# radiomodul.net
KiCad netlist of a schematic drawn in EAGLE
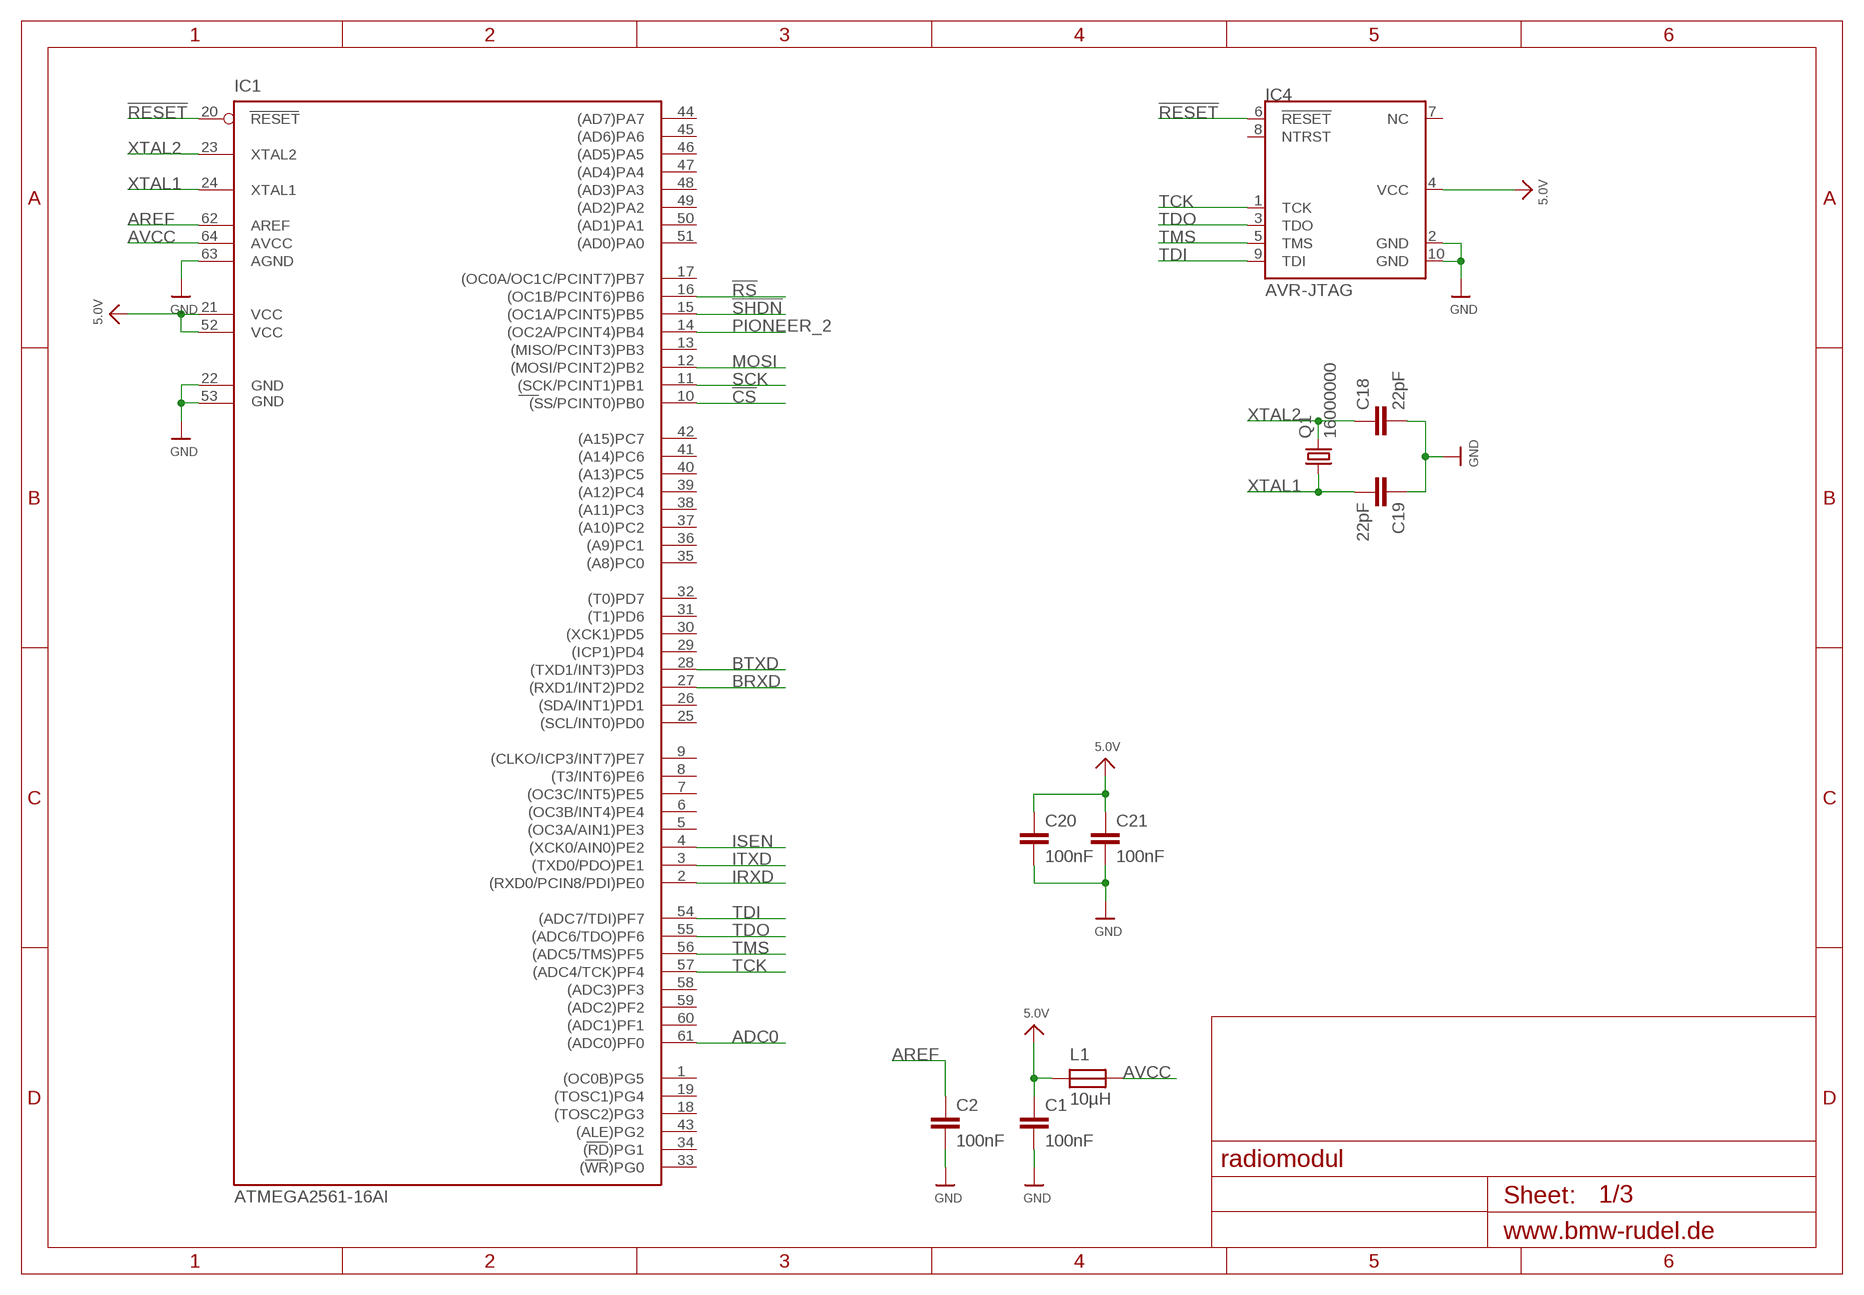
[diagram p0: schematic, sheet 1]
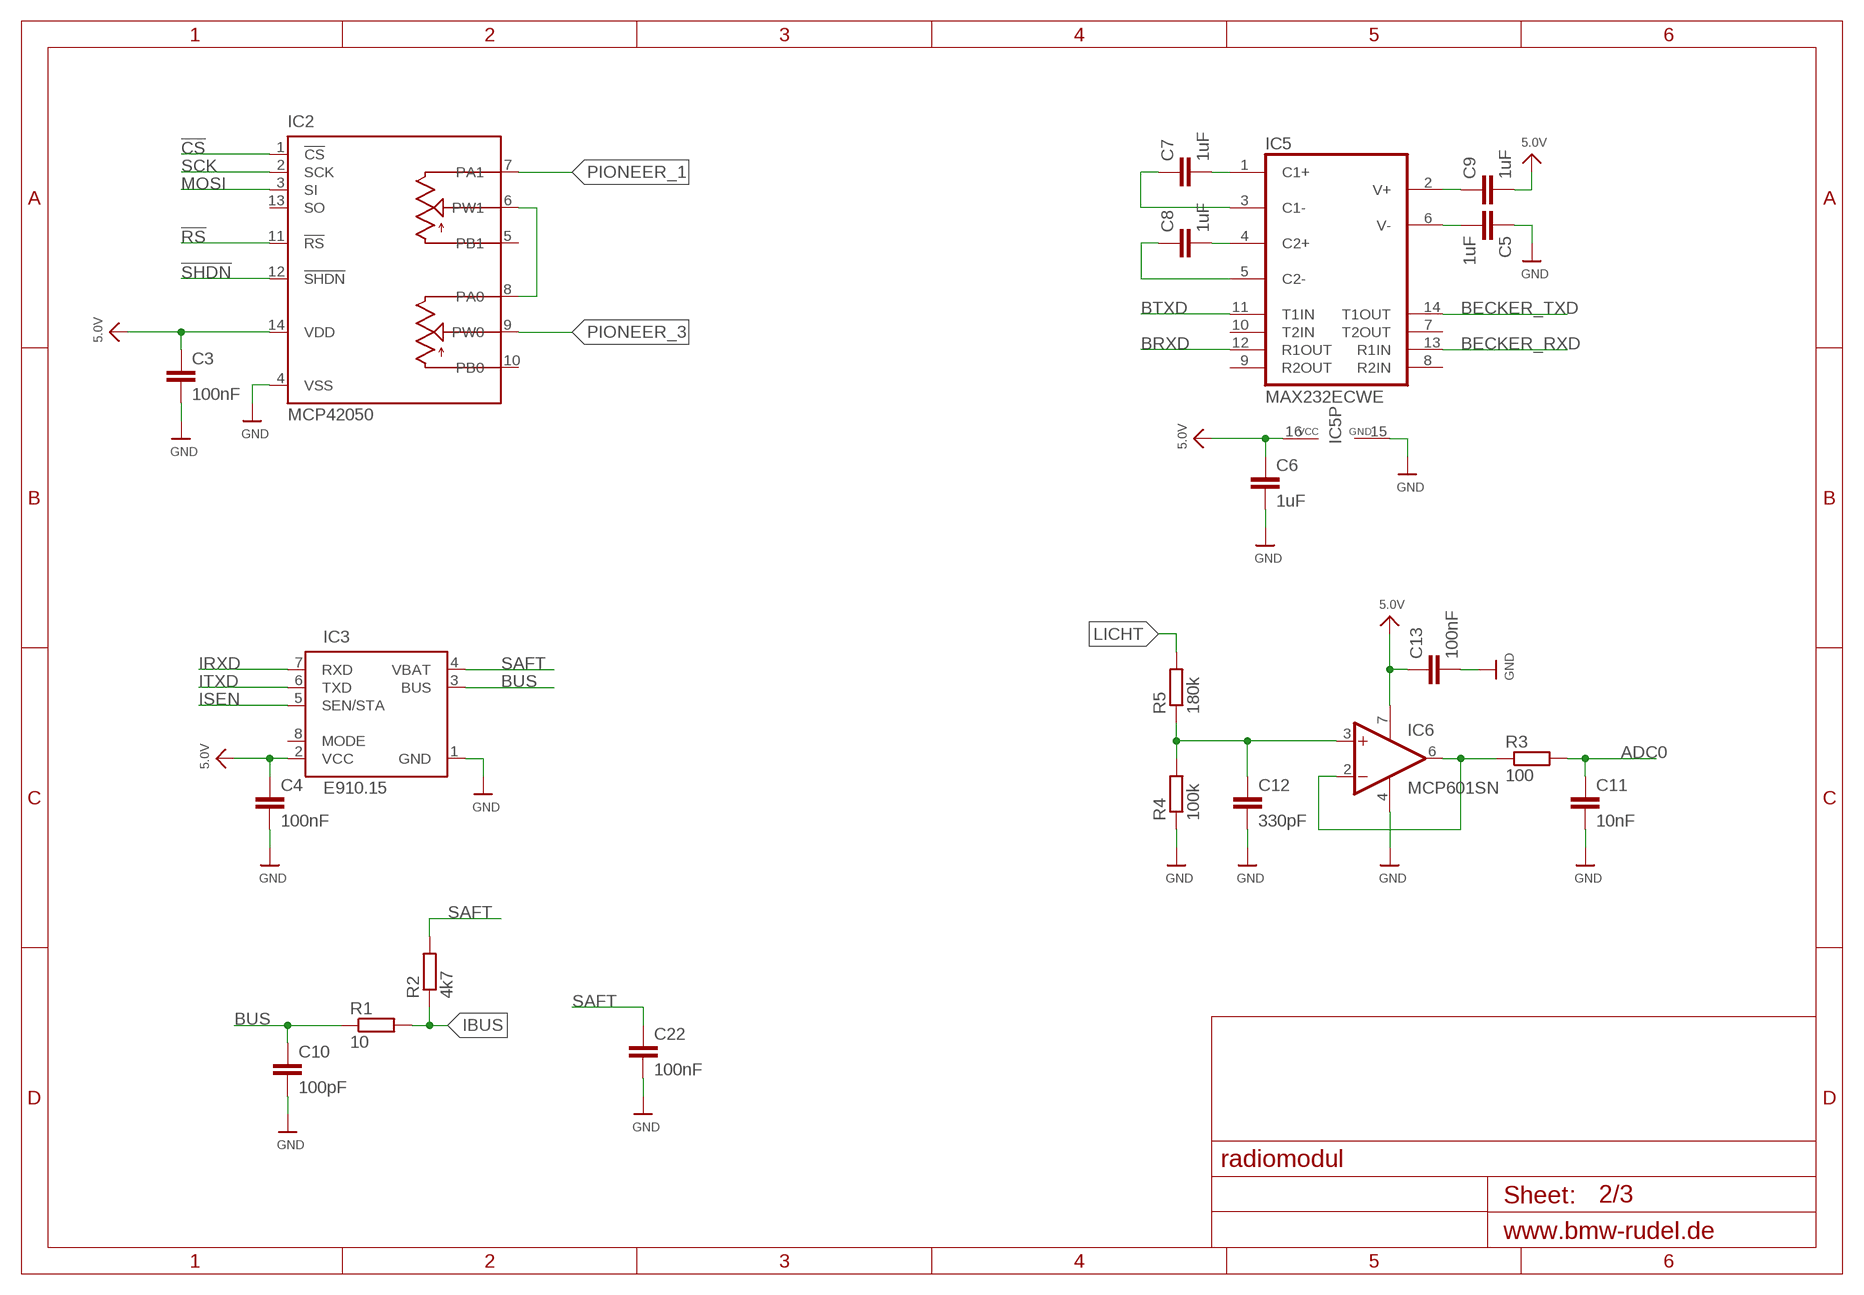
[diagram p1: schematic, sheet 2]
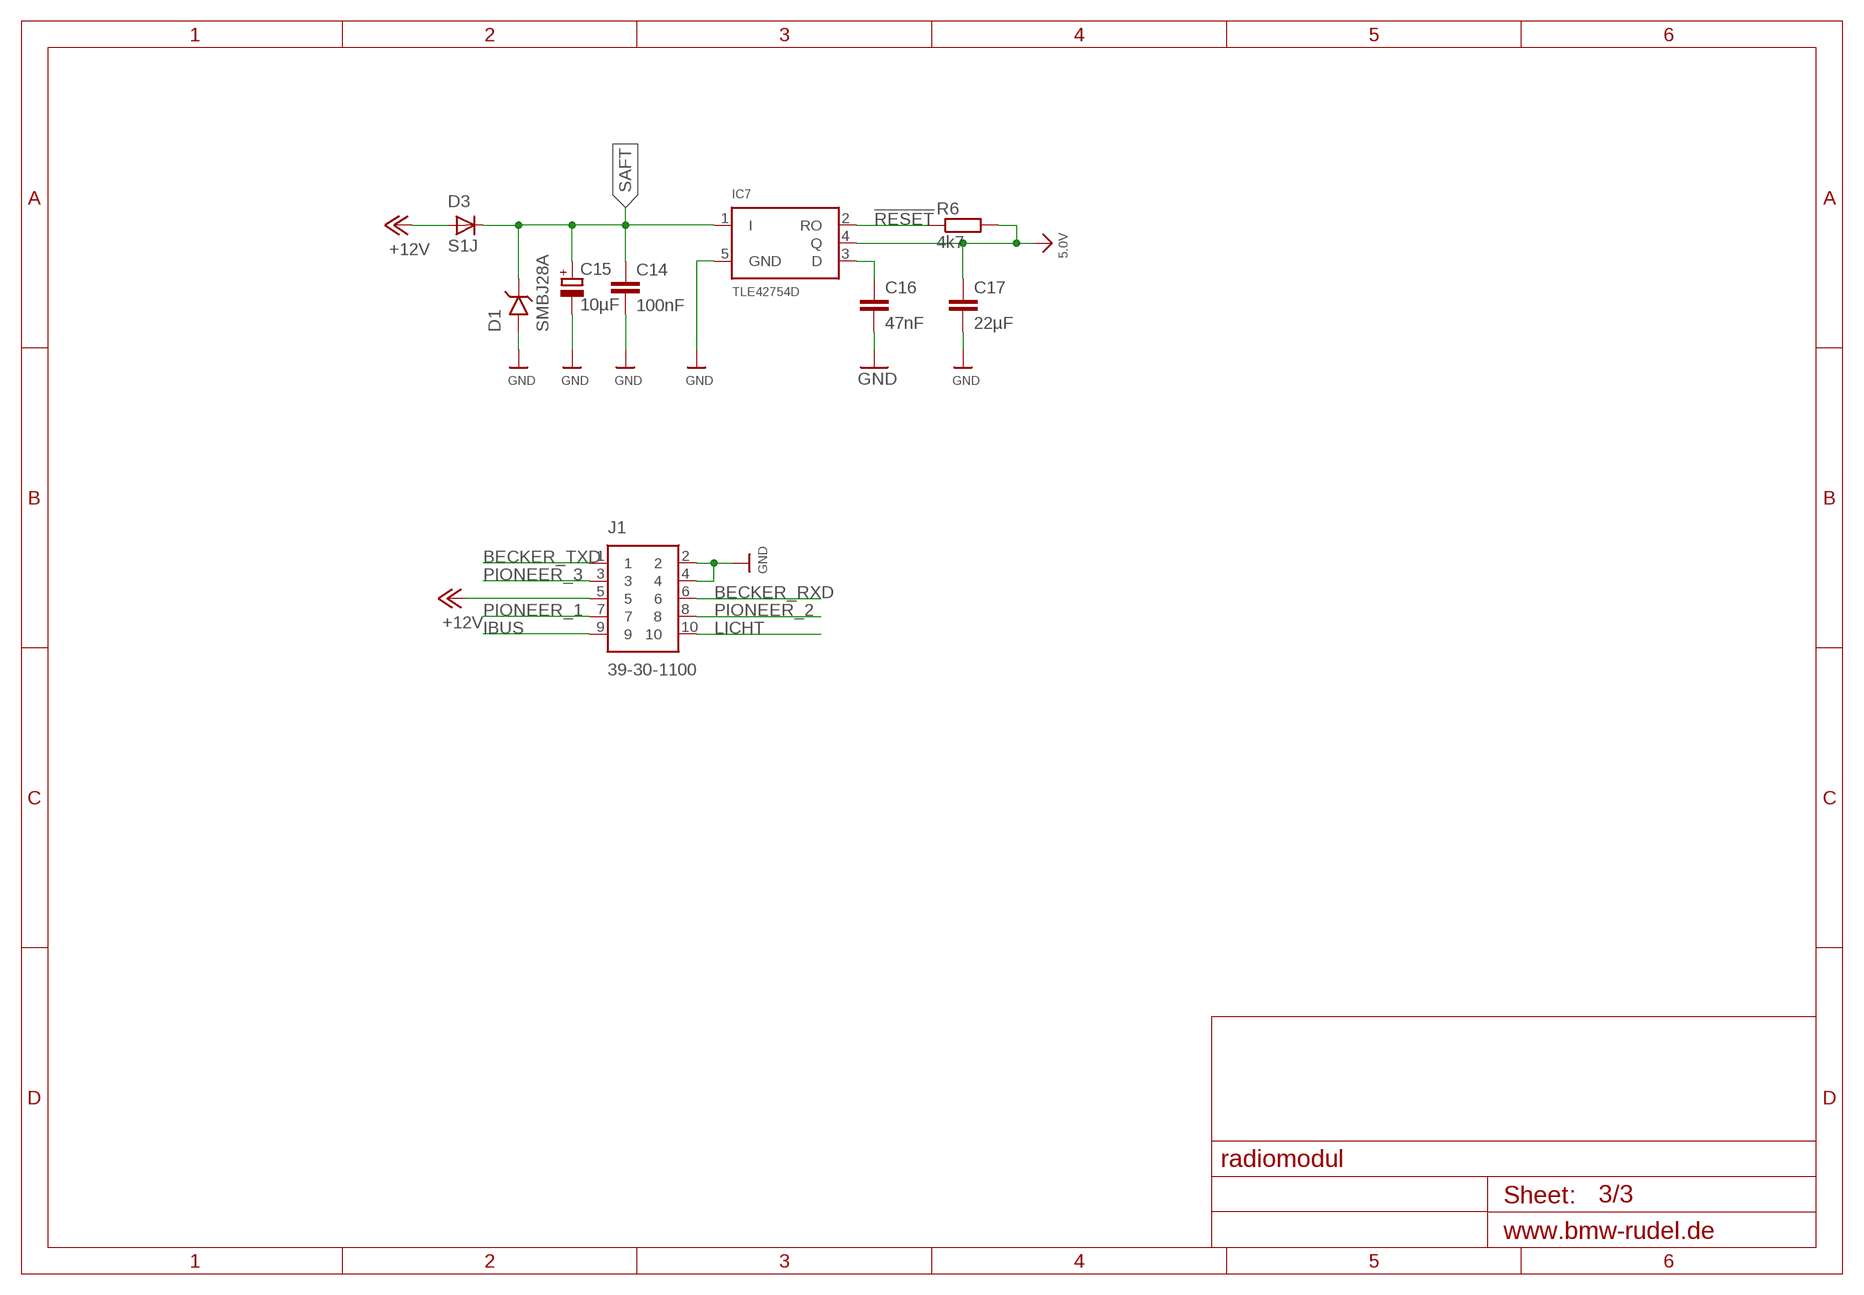
[diagram p2: schematic, sheet 3]

(export (version "E")
  (design (tool "Eeschema 10.0.6"))
  (components
    (comp (ref "C14")
      (value "100nF")
      (footprint "eagle-import:C0805")
      (libsource (lib "eagle-import") (part "C-EUC0805"))
    )
    (comp (ref "C15")
      (value "10µF")
      (footprint "eagle-import:PANASONIC_D")
      (libsource (lib "eagle-import") (part "CPOL-EUD"))
    )
    (comp (ref "C16")
      (value "47nF")
      (footprint "eagle-import:C0805")
      (libsource (lib "eagle-import") (part "C-EUC0805"))
    )
    (comp (ref "C17")
      (value "22µF")
      (footprint "eagle-import:C1206")
      (libsource (lib "eagle-import") (part "C-EUC1206"))
    )
    (comp (ref "D1")
      (value "SMBJ28A")
      (footprint "eagle-import:DO-214AA")
      (libsource (lib "eagle-import") (part "P6SMBXXASMB"))
    )
    (comp (ref "D3")
      (value "S1J")
      (footprint "eagle-import:SMADIODE")
      (libsource (lib "eagle-import") (part "DIODESMA"))
    )
    (comp (ref "IC7")
      (value "TLE42754D")
      (footprint "eagle-import:TO252-51")
      (libsource (lib "eagle-import") (part "TLE42754D"))
    )
    (comp (ref "J1")
      (value "39-30-1100")
      (footprint "eagle-import:39-30-1100")
      (fields (field (name "MOUSER_PART_NUMBER") "538-39-30-1100") (field (name "RS_PART_NUMBER") "5109871P"))
      (libsource (lib "eagle-import") (part "39-30-1100"))
    )
    (comp (ref "R6")
      (value "4k7")
      (footprint "eagle-import:R0805")
      (libsource (lib "eagle-import") (part "R-EU_R0805"))
    )
    (comp (ref "C3")
      (value "100nF")
      (footprint "eagle-import:C0805")
      (libsource (lib "eagle-import") (part "C-EUC0805"))
    )
    (comp (ref "C4")
      (value "100nF")
      (footprint "eagle-import:C0805")
      (libsource (lib "eagle-import") (part "C-EUC0805"))
    )
    (comp (ref "C5")
      (value "1uF")
      (footprint "eagle-import:C0805")
      (libsource (lib "eagle-import") (part "C-EUC0805"))
    )
    (comp (ref "C6")
      (value "1uF")
      (footprint "eagle-import:C0805")
      (libsource (lib "eagle-import") (part "C-EUC0805"))
    )
    (comp (ref "C7")
      (value "1uF")
      (footprint "eagle-import:C0805")
      (libsource (lib "eagle-import") (part "C-EUC0805"))
    )
    (comp (ref "C8")
      (value "1uF")
      (footprint "eagle-import:C0805")
      (libsource (lib "eagle-import") (part "C-EUC0805"))
    )
    (comp (ref "C9")
      (value "1uF")
      (footprint "eagle-import:C0805")
      (libsource (lib "eagle-import") (part "C-EUC0805"))
    )
    (comp (ref "C10")
      (value "100pF")
      (footprint "eagle-import:C0805")
      (libsource (lib "eagle-import") (part "C-EUC0805"))
    )
    (comp (ref "C11")
      (value "10nF")
      (footprint "eagle-import:C0805")
      (libsource (lib "eagle-import") (part "C-EUC0805"))
    )
    (comp (ref "C12")
      (value "330pF")
      (footprint "eagle-import:C0805")
      (libsource (lib "eagle-import") (part "C-EUC0805"))
    )
    (comp (ref "C13")
      (value "100nF")
      (footprint "eagle-import:C0805")
      (libsource (lib "eagle-import") (part "C-EUC0805"))
    )
    (comp (ref "C22")
      (value "100nF")
      (footprint "eagle-import:C0805")
      (libsource (lib "eagle-import") (part "C-EUC0805"))
    )
    (comp (ref "IC2")
      (value "MCP42050")
      (footprint "eagle-import:SO-14")
      (libsource (lib "eagle-import") (part "MCP42050"))
    )
    (comp (ref "IC3")
      (value "E910.15")
      (footprint "eagle-import:SO8")
      (libsource (lib "eagle-import") (part "E910.15"))
    )
    (comp (ref "IC5")
      (value "MAX232ECWE")
      (footprint "eagle-import:SO16L")
      (fields (field (name "MF") "MAXIM") (field (name "MPN") "MAX232ECWE+"))
      (libsource (lib "eagle-import") (part "MAX232ECWE"))
    )
    (comp (ref "IC6")
      (value "MCP601SN")
      (footprint "eagle-import:SO08")
      (libsource (lib "eagle-import") (part "MCP601SN"))
    )
    (comp (ref "R1")
      (value "10")
      (footprint "eagle-import:R0805")
      (libsource (lib "eagle-import") (part "R-EU_R0805"))
    )
    (comp (ref "R2")
      (value "4k7")
      (footprint "eagle-import:R0805")
      (libsource (lib "eagle-import") (part "R-EU_R0805"))
    )
    (comp (ref "R3")
      (value "100")
      (footprint "eagle-import:R0805")
      (libsource (lib "eagle-import") (part "R-EU_R0805"))
    )
    (comp (ref "R4")
      (value "100k")
      (footprint "eagle-import:R0805")
      (libsource (lib "eagle-import") (part "R-EU_R0805"))
    )
    (comp (ref "R5")
      (value "180k")
      (footprint "eagle-import:R0805")
      (libsource (lib "eagle-import") (part "R-EU_R0805"))
    )
    (comp (ref "C1")
      (value "100nF")
      (footprint "eagle-import:C0805")
      (libsource (lib "eagle-import") (part "C-EUC0805"))
    )
    (comp (ref "C2")
      (value "100nF")
      (footprint "eagle-import:C0805")
      (libsource (lib "eagle-import") (part "C-EUC0805"))
    )
    (comp (ref "C18")
      (value "22pF")
      (footprint "eagle-import:C0805")
      (libsource (lib "eagle-import") (part "C-EUC0805"))
    )
    (comp (ref "C19")
      (value "22pF")
      (footprint "eagle-import:C0805")
      (libsource (lib "eagle-import") (part "C-EUC0805"))
    )
    (comp (ref "C20")
      (value "100nF")
      (footprint "eagle-import:C0805")
      (libsource (lib "eagle-import") (part "C-EUC0805"))
    )
    (comp (ref "C21")
      (value "100nF")
      (footprint "eagle-import:C0805")
      (libsource (lib "eagle-import") (part "C-EUC0805"))
    )
    (comp (ref "IC1")
      (value "ATMEGA2561-16AI")
      (footprint "eagle-import:TQFP64")
      (libsource (lib "eagle-import") (part "ATMEGA2561AI-16"))
    )
    (comp (ref "IC4")
      (value "AVR-JTAG")
      (footprint "eagle-import:2X05_1.27MM_SMT")
      (libsource (lib "eagle-import") (part "AVR-JTAG"))
    )
    (comp (ref "L1")
      (value "10µH")
      (footprint "eagle-import:1206")
      (libsource (lib "eagle-import") (part "FERRITE1206"))
    )
    (comp (ref "Q1")
      (value "16000000")
      (footprint "eagle-import:HC49UP")
      (libsource (lib "eagle-import") (part "CRYSTALHC49UP"))
    )
  )
  (nets
    (net (code "1") (name "+12V") (class "Default")
      (node (ref "D3") (pin "A") (pinfunction "A_A") (pintype "passive"))
      (node (ref "J1") (pin "5") (pinfunction "5_5") (pintype "bidirectional"))
    )
    (net (code "2") (name "5.0V") (class "Default")
      (node (ref "C1") (pin "1") (pinfunction "1_1") (pintype "passive"))
      (node (ref "C13") (pin "1") (pinfunction "1_1") (pintype "passive"))
      (node (ref "C17") (pin "1") (pinfunction "1_1") (pintype "passive"))
      (node (ref "C20") (pin "1") (pinfunction "1_1") (pintype "passive"))
      (node (ref "C21") (pin "1") (pinfunction "1_1") (pintype "passive"))
      (node (ref "C3") (pin "1") (pinfunction "1_1") (pintype "passive"))
      (node (ref "C4") (pin "1") (pinfunction "1_1") (pintype "passive"))
      (node (ref "C6") (pin "1") (pinfunction "1_1") (pintype "passive"))
      (node (ref "C9") (pin "2") (pinfunction "2_2") (pintype "passive"))
      (node (ref "IC1") (pin "21") (pinfunction "VCC_21") (pintype "power_in"))
      (node (ref "IC1") (pin "52") (pinfunction "VCC1_52") (pintype "power_in"))
      (node (ref "IC2") (pin "14") (pinfunction "VDD_14") (pintype "power_in"))
      (node (ref "IC3") (pin "2") (pinfunction "VCC_2") (pintype "power_in"))
      (node (ref "IC4") (pin "4") (pinfunction "VCC_4") (pintype "bidirectional"))
      (node (ref "IC5") (pin "16") (pinfunction "VCC_16") (pintype "power_in"))
      (node (ref "IC6") (pin "7") (pinfunction "V+_7") (pintype "power_in"))
      (node (ref "IC7") (pin "4") (pinfunction "Q_4") (pintype "bidirectional"))
      (node (ref "L1") (pin "1") (pinfunction "P$1_1") (pintype "bidirectional"))
      (node (ref "R6") (pin "2") (pinfunction "2_2") (pintype "passive"))
    )
    (net (code "3") (name "ADC0") (class "Default")
      (node (ref "C11") (pin "1") (pinfunction "1_1") (pintype "passive"))
      (node (ref "IC1") (pin "61") (pinfunction "(ADC0)PF0_61") (pintype "bidirectional"))
      (node (ref "R3") (pin "2") (pinfunction "2_2") (pintype "passive"))
    )
    (net (code "4") (name "AREF") (class "Default")
      (node (ref "C2") (pin "1") (pinfunction "1_1") (pintype "passive"))
      (node (ref "IC1") (pin "62") (pinfunction "AREF_62") (pintype "bidirectional"))
    )
    (net (code "5") (name "AVCC") (class "Default")
      (node (ref "IC1") (pin "64") (pinfunction "AVCC_64") (pintype "power_in"))
      (node (ref "L1") (pin "2") (pinfunction "P$2_2") (pintype "bidirectional"))
    )
    (net (code "6") (name "BECKER_RXD") (class "Default")
      (node (ref "IC5") (pin "13") (pinfunction "R1IN_13") (pintype "input"))
      (node (ref "J1") (pin "6") (pinfunction "6_6") (pintype "bidirectional"))
    )
    (net (code "7") (name "BECKER_TXD") (class "Default")
      (node (ref "IC5") (pin "14") (pinfunction "T1OUT_14") (pintype "output"))
      (node (ref "J1") (pin "1") (pinfunction "1_1") (pintype "bidirectional"))
    )
    (net (code "8") (name "BRXD") (class "Default")
      (node (ref "IC1") (pin "27") (pinfunction "(RXD1/INT2)PD2_27") (pintype "bidirectional"))
      (node (ref "IC5") (pin "12") (pinfunction "R1OUT_12") (pintype "output"))
    )
    (net (code "9") (name "BTXD") (class "Default")
      (node (ref "IC1") (pin "28") (pinfunction "(TXD1/INT3)PD3_28") (pintype "bidirectional"))
      (node (ref "IC5") (pin "11") (pinfunction "T1IN_11") (pintype "input"))
    )
    (net (code "10") (name "BUS") (class "Default")
      (node (ref "C10") (pin "1") (pinfunction "1_1") (pintype "passive"))
      (node (ref "IC3") (pin "3") (pinfunction "BUS_3") (pintype "bidirectional"))
      (node (ref "R1") (pin "1") (pinfunction "1_1") (pintype "passive"))
    )
    (net (code "11") (name "GND") (class "Default")
      (node (ref "C1") (pin "2") (pinfunction "2_2") (pintype "passive"))
      (node (ref "C10") (pin "2") (pinfunction "2_2") (pintype "passive"))
      (node (ref "C11") (pin "2") (pinfunction "2_2") (pintype "passive"))
      (node (ref "C12") (pin "2") (pinfunction "2_2") (pintype "passive"))
      (node (ref "C13") (pin "2") (pinfunction "2_2") (pintype "passive"))
      (node (ref "C14") (pin "2") (pinfunction "2_2") (pintype "passive"))
      (node (ref "C15") (pin "-") (pinfunction "-_-") (pintype "passive"))
      (node (ref "C16") (pin "2") (pinfunction "2_2") (pintype "passive"))
      (node (ref "C17") (pin "2") (pinfunction "2_2") (pintype "passive"))
      (node (ref "C18") (pin "2") (pinfunction "2_2") (pintype "passive"))
      (node (ref "C19") (pin "1") (pinfunction "1_1") (pintype "passive"))
      (node (ref "C2") (pin "2") (pinfunction "2_2") (pintype "passive"))
      (node (ref "C20") (pin "2") (pinfunction "2_2") (pintype "passive"))
      (node (ref "C21") (pin "2") (pinfunction "2_2") (pintype "passive"))
      (node (ref "C22") (pin "2") (pinfunction "2_2") (pintype "passive"))
      (node (ref "C3") (pin "2") (pinfunction "2_2") (pintype "passive"))
      (node (ref "C4") (pin "2") (pinfunction "2_2") (pintype "passive"))
      (node (ref "C5") (pin "1") (pinfunction "1_1") (pintype "passive"))
      (node (ref "C6") (pin "2") (pinfunction "2_2") (pintype "passive"))
      (node (ref "D1") (pin "P$2") (pinfunction "A_P$2") (pintype "passive"))
      (node (ref "IC1") (pin "22") (pinfunction "GND_22") (pintype "power_in"))
      (node (ref "IC1") (pin "53") (pinfunction "GND1_53") (pintype "power_in"))
      (node (ref "IC1") (pin "63") (pinfunction "AGND_63") (pintype "power_in"))
      (node (ref "IC2") (pin "4") (pinfunction "VSS_4") (pintype "power_in"))
      (node (ref "IC3") (pin "1") (pinfunction "GND_1") (pintype "power_in"))
      (node (ref "IC4") (pin "10") (pinfunction "GND_10") (pintype "bidirectional"))
      (node (ref "IC4") (pin "2") (pinfunction "GND_2") (pintype "bidirectional"))
      (node (ref "IC5") (pin "15") (pinfunction "GND_15") (pintype "power_in"))
      (node (ref "IC6") (pin "4") (pinfunction "V-_4") (pintype "power_in"))
      (node (ref "IC7") (pin "5") (pinfunction "GND_5") (pintype "bidirectional"))
      (node (ref "J1") (pin "2") (pinfunction "2_2") (pintype "bidirectional"))
      (node (ref "J1") (pin "4") (pinfunction "4_4") (pintype "bidirectional"))
      (node (ref "R4") (pin "1") (pinfunction "1_1") (pintype "passive"))
    )
    (net (code "12") (name "IBUS") (class "Default")
      (node (ref "J1") (pin "9") (pinfunction "9_9") (pintype "bidirectional"))
      (node (ref "R1") (pin "2") (pinfunction "2_2") (pintype "passive"))
      (node (ref "R2") (pin "1") (pinfunction "1_1") (pintype "passive"))
    )
    (net (code "13") (name "IRXD") (class "Default")
      (node (ref "IC1") (pin "2") (pinfunction "(RXD0/PCIN8/PDI)PE0_2") (pintype "bidirectional"))
      (node (ref "IC3") (pin "7") (pinfunction "RXD_7") (pintype "output"))
    )
    (net (code "14") (name "ISEN") (class "Default")
      (node (ref "IC1") (pin "4") (pinfunction "(XCK0/AIN0)PE2_4") (pintype "bidirectional"))
      (node (ref "IC3") (pin "5") (pinfunction "SEN/STA_5") (pintype "bidirectional"))
    )
    (net (code "15") (name "ITXD") (class "Default")
      (node (ref "IC1") (pin "3") (pinfunction "(TXD0/PDO)PE1_3") (pintype "bidirectional"))
      (node (ref "IC3") (pin "6") (pinfunction "TXD_6") (pintype "input"))
    )
    (net (code "16") (name "LICHT") (class "Default")
      (node (ref "J1") (pin "10") (pinfunction "10_10") (pintype "bidirectional"))
      (node (ref "R5") (pin "2") (pinfunction "2_2") (pintype "passive"))
    )
    (net (code "17") (name "MOSI") (class "Default")
      (node (ref "IC1") (pin "12") (pinfunction "(MOSI/PCINT2)PB2_12") (pintype "bidirectional"))
      (node (ref "IC2") (pin "3") (pinfunction "SI_3") (pintype "input"))
    )
    (net (code "18") (name "Net-(IC2-PA0)") (class "Default")
      (node (ref "IC2") (pin "6") (pinfunction "PW1_6") (pintype "bidirectional"))
      (node (ref "IC2") (pin "8") (pinfunction "PA0_8") (pintype "bidirectional"))
    )
    (net (code "19") (name "Net-(IC5A-C1+)") (class "Default")
      (node (ref "C7") (pin "2") (pinfunction "2_2") (pintype "passive"))
      (node (ref "IC5") (pin "1") (pinfunction "C1+_1") (pintype "bidirectional"))
    )
    (net (code "20") (name "Net-(IC5A-C1-)") (class "Default")
      (node (ref "C7") (pin "1") (pinfunction "1_1") (pintype "passive"))
      (node (ref "IC5") (pin "3") (pinfunction "C1-_3") (pintype "bidirectional"))
    )
    (net (code "21") (name "Net-(IC5A-C2+)") (class "Default")
      (node (ref "C8") (pin "2") (pinfunction "2_2") (pintype "passive"))
      (node (ref "IC5") (pin "4") (pinfunction "C2+_4") (pintype "bidirectional"))
    )
    (net (code "22") (name "Net-(IC5A-C2-)") (class "Default")
      (node (ref "C8") (pin "1") (pinfunction "1_1") (pintype "passive"))
      (node (ref "IC5") (pin "5") (pinfunction "C2-_5") (pintype "bidirectional"))
    )
    (net (code "23") (name "Net-(IC5A-V+)") (class "Default")
      (node (ref "C9") (pin "1") (pinfunction "1_1") (pintype "passive"))
      (node (ref "IC5") (pin "2") (pinfunction "V+_2") (pintype "bidirectional"))
    )
    (net (code "24") (name "Net-(IC5A-V-)") (class "Default")
      (node (ref "C5") (pin "2") (pinfunction "2_2") (pintype "passive"))
      (node (ref "IC5") (pin "6") (pinfunction "V-_6") (pintype "bidirectional"))
    )
    (net (code "25") (name "Net-(IC6-+IN)") (class "Default")
      (node (ref "C12") (pin "1") (pinfunction "1_1") (pintype "passive"))
      (node (ref "IC6") (pin "3") (pinfunction "+IN_3") (pintype "input"))
      (node (ref "R4") (pin "2") (pinfunction "2_2") (pintype "passive"))
      (node (ref "R5") (pin "1") (pinfunction "1_1") (pintype "passive"))
    )
    (net (code "26") (name "Net-(IC6--IN)") (class "Default")
      (node (ref "IC6") (pin "2") (pinfunction "-IN_2") (pintype "input"))
      (node (ref "IC6") (pin "6") (pinfunction "OUT_6") (pintype "output"))
      (node (ref "R3") (pin "1") (pinfunction "1_1") (pintype "passive"))
    )
    (net (code "27") (name "Net-(IC7-D)") (class "Default")
      (node (ref "C16") (pin "1") (pinfunction "1_1") (pintype "passive"))
      (node (ref "IC7") (pin "3") (pinfunction "D_3") (pintype "bidirectional"))
    )
    (net (code "28") (name "PIONEER_1") (class "Default")
      (node (ref "IC2") (pin "7") (pinfunction "PA1_7") (pintype "bidirectional"))
      (node (ref "J1") (pin "7") (pinfunction "7_7") (pintype "bidirectional"))
    )
    (net (code "29") (name "PIONEER_2") (class "Default")
      (node (ref "IC1") (pin "14") (pinfunction "(OC2A/PCINT4)PB4_14") (pintype "bidirectional"))
      (node (ref "J1") (pin "8") (pinfunction "8_8") (pintype "bidirectional"))
    )
    (net (code "30") (name "PIONEER_3") (class "Default")
      (node (ref "IC2") (pin "9") (pinfunction "PW0_9") (pintype "bidirectional"))
      (node (ref "J1") (pin "3") (pinfunction "3_3") (pintype "bidirectional"))
    )
    (net (code "31") (name "SAFT") (class "Default")
      (node (ref "C14") (pin "1") (pinfunction "1_1") (pintype "passive"))
      (node (ref "C15") (pin "+") (pinfunction "+_+") (pintype "passive"))
      (node (ref "C22") (pin "1") (pinfunction "1_1") (pintype "passive"))
      (node (ref "D1") (pin "P$1") (pinfunction "C_P$1") (pintype "passive"))
      (node (ref "D3") (pin "C") (pinfunction "C_C") (pintype "passive"))
      (node (ref "IC3") (pin "4") (pinfunction "VBAT_4") (pintype "power_in"))
      (node (ref "IC7") (pin "1") (pinfunction "I_1") (pintype "bidirectional"))
      (node (ref "R2") (pin "2") (pinfunction "2_2") (pintype "passive"))
    )
    (net (code "32") (name "SCK") (class "Default")
      (node (ref "IC1") (pin "11") (pinfunction "(SCK/PCINT1)PB1_11") (pintype "bidirectional"))
      (node (ref "IC2") (pin "2") (pinfunction "SCK_2") (pintype "input"))
    )
    (net (code "33") (name "TCK") (class "Default")
      (node (ref "IC1") (pin "57") (pinfunction "(ADC4/TCK)PF4_57") (pintype "bidirectional"))
      (node (ref "IC4") (pin "1") (pinfunction "TCK_1") (pintype "bidirectional"))
    )
    (net (code "34") (name "TDI") (class "Default")
      (node (ref "IC1") (pin "54") (pinfunction "(ADC7/TDI)PF7_54") (pintype "bidirectional"))
      (node (ref "IC4") (pin "9") (pinfunction "TDI_9") (pintype "bidirectional"))
    )
    (net (code "35") (name "TDO") (class "Default")
      (node (ref "IC1") (pin "55") (pinfunction "(ADC6/TDO)PF6_55") (pintype "bidirectional"))
      (node (ref "IC4") (pin "3") (pinfunction "TDO_3") (pintype "bidirectional"))
    )
    (net (code "36") (name "TMS") (class "Default")
      (node (ref "IC1") (pin "56") (pinfunction "(ADC5/TMS)PF5_56") (pintype "bidirectional"))
      (node (ref "IC4") (pin "5") (pinfunction "TMS_5") (pintype "bidirectional"))
    )
    (net (code "37") (name "XTAL1") (class "Default")
      (node (ref "C19") (pin "2") (pinfunction "2_2") (pintype "passive"))
      (node (ref "IC1") (pin "24") (pinfunction "XTAL1_24") (pintype "input"))
      (node (ref "Q1") (pin "1") (pinfunction "1_1") (pintype "passive"))
    )
    (net (code "38") (name "XTAL2") (class "Default")
      (node (ref "C18") (pin "1") (pinfunction "1_1") (pintype "passive"))
      (node (ref "IC1") (pin "23") (pinfunction "XTAL2_23") (pintype "output"))
      (node (ref "Q1") (pin "2") (pinfunction "2_2") (pintype "passive"))
    )
    (net (code "39") (name "unconnected-(IC1-(A8)PC0-Pad35)") (class "Default")
      (node (ref "IC1") (pin "35") (pinfunction "(A8)PC0_35") (pintype "bidirectional"))
    )
    (net (code "40") (name "unconnected-(IC1-(A9)PC1-Pad36)") (class "Default")
      (node (ref "IC1") (pin "36") (pinfunction "(A9)PC1_36") (pintype "bidirectional"))
    )
    (net (code "41") (name "unconnected-(IC1-(A10)PC2-Pad37)") (class "Default")
      (node (ref "IC1") (pin "37") (pinfunction "(A10)PC2_37") (pintype "bidirectional"))
    )
    (net (code "42") (name "unconnected-(IC1-(A11)PC3-Pad38)") (class "Default")
      (node (ref "IC1") (pin "38") (pinfunction "(A11)PC3_38") (pintype "bidirectional"))
    )
    (net (code "43") (name "unconnected-(IC1-(A12)PC4-Pad39)") (class "Default")
      (node (ref "IC1") (pin "39") (pinfunction "(A12)PC4_39") (pintype "bidirectional"))
    )
    (net (code "44") (name "unconnected-(IC1-(A13)PC5-Pad40)") (class "Default")
      (node (ref "IC1") (pin "40") (pinfunction "(A13)PC5_40") (pintype "bidirectional"))
    )
    (net (code "45") (name "unconnected-(IC1-(A14)PC6-Pad41)") (class "Default")
      (node (ref "IC1") (pin "41") (pinfunction "(A14)PC6_41") (pintype "bidirectional"))
    )
    (net (code "46") (name "unconnected-(IC1-(A15)PC7-Pad42)") (class "Default")
      (node (ref "IC1") (pin "42") (pinfunction "(A15)PC7_42") (pintype "bidirectional"))
    )
    (net (code "47") (name "unconnected-(IC1-(AD0)PA0-Pad51)") (class "Default")
      (node (ref "IC1") (pin "51") (pinfunction "(AD0)PA0_51") (pintype "bidirectional"))
    )
    (net (code "48") (name "unconnected-(IC1-(AD1)PA1-Pad50)") (class "Default")
      (node (ref "IC1") (pin "50") (pinfunction "(AD1)PA1_50") (pintype "bidirectional"))
    )
    (net (code "49") (name "unconnected-(IC1-(AD2)PA2-Pad49)") (class "Default")
      (node (ref "IC1") (pin "49") (pinfunction "(AD2)PA2_49") (pintype "bidirectional"))
    )
    (net (code "50") (name "unconnected-(IC1-(AD3)PA3-Pad48)") (class "Default")
      (node (ref "IC1") (pin "48") (pinfunction "(AD3)PA3_48") (pintype "bidirectional"))
    )
    (net (code "51") (name "unconnected-(IC1-(AD4)PA4-Pad47)") (class "Default")
      (node (ref "IC1") (pin "47") (pinfunction "(AD4)PA4_47") (pintype "bidirectional"))
    )
    (net (code "52") (name "unconnected-(IC1-(AD5)PA5-Pad46)") (class "Default")
      (node (ref "IC1") (pin "46") (pinfunction "(AD5)PA5_46") (pintype "bidirectional"))
    )
    (net (code "53") (name "unconnected-(IC1-(AD6)PA6-Pad45)") (class "Default")
      (node (ref "IC1") (pin "45") (pinfunction "(AD6)PA6_45") (pintype "bidirectional"))
    )
    (net (code "54") (name "unconnected-(IC1-(AD7)PA7-Pad44)") (class "Default")
      (node (ref "IC1") (pin "44") (pinfunction "(AD7)PA7_44") (pintype "bidirectional"))
    )
    (net (code "55") (name "unconnected-(IC1-(ADC1)PF1-Pad60)") (class "Default")
      (node (ref "IC1") (pin "60") (pinfunction "(ADC1)PF1_60") (pintype "bidirectional"))
    )
    (net (code "56") (name "unconnected-(IC1-(ADC2)PF2-Pad59)") (class "Default")
      (node (ref "IC1") (pin "59") (pinfunction "(ADC2)PF2_59") (pintype "bidirectional"))
    )
    (net (code "57") (name "unconnected-(IC1-(ADC3)PF3-Pad58)") (class "Default")
      (node (ref "IC1") (pin "58") (pinfunction "(ADC3)PF3_58") (pintype "bidirectional"))
    )
    (net (code "58") (name "unconnected-(IC1-(ALE)PG2-Pad43)") (class "Default")
      (node (ref "IC1") (pin "43") (pinfunction "(ALE)PG2_43") (pintype "bidirectional"))
    )
    (net (code "59") (name "unconnected-(IC1-(CLKO{slash}ICP3{slash}INT7)PE7-Pad9)") (class "Default")
      (node (ref "IC1") (pin "9") (pinfunction "(CLKO/ICP3/INT7)PE7_9") (pintype "bidirectional"))
    )
    (net (code "60") (name "unconnected-(IC1-(ICP1)PD4-Pad29)") (class "Default")
      (node (ref "IC1") (pin "29") (pinfunction "(ICP1)PD4_29") (pintype "bidirectional"))
    )
    (net (code "61") (name "unconnected-(IC1-(MISO{slash}PCINT3)PB3-Pad13)") (class "Default")
      (node (ref "IC1") (pin "13") (pinfunction "(MISO/PCINT3)PB3_13") (pintype "bidirectional"))
    )
    (net (code "62") (name "unconnected-(IC1-(OC0A{slash}OC1C{slash}PCINT7)PB7-Pad17)") (class "Default")
      (node (ref "IC1") (pin "17") (pinfunction "(OC0A/OC1C/PCINT7)PB7_17") (pintype "bidirectional"))
    )
    (net (code "63") (name "unconnected-(IC1-(OC0B)PG5-Pad1)") (class "Default")
      (node (ref "IC1") (pin "1") (pinfunction "(OC0B)PG5_1") (pintype "bidirectional"))
    )
    (net (code "64") (name "unconnected-(IC1-(OC3A{slash}AIN1)PE3-Pad5)") (class "Default")
      (node (ref "IC1") (pin "5") (pinfunction "(OC3A/AIN1)PE3_5") (pintype "bidirectional"))
    )
    (net (code "65") (name "unconnected-(IC1-(OC3B{slash}INT4)PE4-Pad6)") (class "Default")
      (node (ref "IC1") (pin "6") (pinfunction "(OC3B/INT4)PE4_6") (pintype "bidirectional"))
    )
    (net (code "66") (name "unconnected-(IC1-(OC3C{slash}INT5)PE5-Pad7)") (class "Default")
      (node (ref "IC1") (pin "7") (pinfunction "(OC3C/INT5)PE5_7") (pintype "bidirectional"))
    )
    (net (code "67") (name "unconnected-(IC1-(RD)PG1-Pad34)") (class "Default")
      (node (ref "IC1") (pin "34") (pinfunction "(RD)PG1_34") (pintype "bidirectional"))
    )
    (net (code "68") (name "unconnected-(IC1-(SCL{slash}INT0)PD0-Pad25)") (class "Default")
      (node (ref "IC1") (pin "25") (pinfunction "(SCL/INT0)PD0_25") (pintype "bidirectional"))
    )
    (net (code "69") (name "unconnected-(IC1-(SDA{slash}INT1)PD1-Pad26)") (class "Default")
      (node (ref "IC1") (pin "26") (pinfunction "(SDA/INT1)PD1_26") (pintype "bidirectional"))
    )
    (net (code "70") (name "unconnected-(IC1-(T0)PD7-Pad32)") (class "Default")
      (node (ref "IC1") (pin "32") (pinfunction "(T0)PD7_32") (pintype "bidirectional"))
    )
    (net (code "71") (name "unconnected-(IC1-(T1)PD6-Pad31)") (class "Default")
      (node (ref "IC1") (pin "31") (pinfunction "(T1)PD6_31") (pintype "bidirectional"))
    )
    (net (code "72") (name "unconnected-(IC1-(T3{slash}INT6)PE6-Pad8)") (class "Default")
      (node (ref "IC1") (pin "8") (pinfunction "(T3/INT6)PE6_8") (pintype "bidirectional"))
    )
    (net (code "73") (name "unconnected-(IC1-(TOSC1)PG4-Pad19)") (class "Default")
      (node (ref "IC1") (pin "19") (pinfunction "(TOSC1)PG4_19") (pintype "bidirectional"))
    )
    (net (code "74") (name "unconnected-(IC1-(TOSC2)PG3-Pad18)") (class "Default")
      (node (ref "IC1") (pin "18") (pinfunction "(TOSC2)PG3_18") (pintype "bidirectional"))
    )
    (net (code "75") (name "unconnected-(IC1-(WR)PG0-Pad33)") (class "Default")
      (node (ref "IC1") (pin "33") (pinfunction "(WR)PG0_33") (pintype "bidirectional"))
    )
    (net (code "76") (name "unconnected-(IC1-(XCK1)PD5-Pad30)") (class "Default")
      (node (ref "IC1") (pin "30") (pinfunction "(XCK1)PD5_30") (pintype "bidirectional"))
    )
    (net (code "77") (name "unconnected-(IC2-PB0-Pad10)") (class "Default")
      (node (ref "IC2") (pin "10") (pinfunction "PB0_10") (pintype "bidirectional"))
    )
    (net (code "78") (name "unconnected-(IC2-PB1-Pad5)") (class "Default")
      (node (ref "IC2") (pin "5") (pinfunction "PB1_5") (pintype "bidirectional"))
    )
    (net (code "79") (name "unconnected-(IC2-SO-Pad13)") (class "Default")
      (node (ref "IC2") (pin "13") (pinfunction "SO_13") (pintype "output"))
    )
    (net (code "80") (name "unconnected-(IC3-MODE-Pad8)") (class "Default")
      (node (ref "IC3") (pin "8") (pinfunction "MODE_8") (pintype "input"))
    )
    (net (code "81") (name "unconnected-(IC4-NC-Pad7)") (class "Default")
      (node (ref "IC4") (pin "7") (pinfunction "NC_7") (pintype "no_connect"))
    )
    (net (code "82") (name "unconnected-(IC4-NTRST-Pad8)") (class "Default")
      (node (ref "IC4") (pin "8") (pinfunction "NTRST_8") (pintype "bidirectional"))
    )
    (net (code "83") (name "unconnected-(IC5A-R2IN-Pad8)") (class "Default")
      (node (ref "IC5") (pin "8") (pinfunction "R2IN_8") (pintype "input"))
    )
    (net (code "84") (name "unconnected-(IC5A-R2OUT-Pad9)") (class "Default")
      (node (ref "IC5") (pin "9") (pinfunction "R2OUT_9") (pintype "output"))
    )
    (net (code "85") (name "unconnected-(IC5A-T2IN-Pad10)") (class "Default")
      (node (ref "IC5") (pin "10") (pinfunction "T2IN_10") (pintype "input"))
    )
    (net (code "86") (name "unconnected-(IC5A-T2OUT-Pad7)") (class "Default")
      (node (ref "IC5") (pin "7") (pinfunction "T2OUT_7") (pintype "output"))
    )
    (net (code "87") (name "~{CS}") (class "Default")
      (node (ref "IC1") (pin "10") (pinfunction "(SS/PCINT0)PB0_10") (pintype "bidirectional"))
      (node (ref "IC2") (pin "1") (pinfunction "~{CS}_1") (pintype "input"))
    )
    (net (code "88") (name "~{RESET}") (class "Default")
      (node (ref "IC1") (pin "20") (pinfunction "RESET_20") (pintype "input"))
      (node (ref "IC4") (pin "6") (pinfunction "~{RESET}_6") (pintype "bidirectional"))
      (node (ref "IC7") (pin "2") (pinfunction "RO_2") (pintype "bidirectional"))
      (node (ref "R6") (pin "1") (pinfunction "1_1") (pintype "passive"))
    )
    (net (code "89") (name "~{RS}") (class "Default")
      (node (ref "IC1") (pin "16") (pinfunction "(OC1B/PCINT6)PB6_16") (pintype "bidirectional"))
      (node (ref "IC2") (pin "11") (pinfunction "~{RS}_11") (pintype "input"))
    )
    (net (code "90") (name "~{SHDN}") (class "Default")
      (node (ref "IC1") (pin "15") (pinfunction "(OC1A/PCINT5)PB5_15") (pintype "bidirectional"))
      (node (ref "IC2") (pin "12") (pinfunction "~{SHDN}_12") (pintype "input"))
    )
  )
)
